# USB2A_CONN.net
KiCad netlist of a schematic drawn in Altium Designer
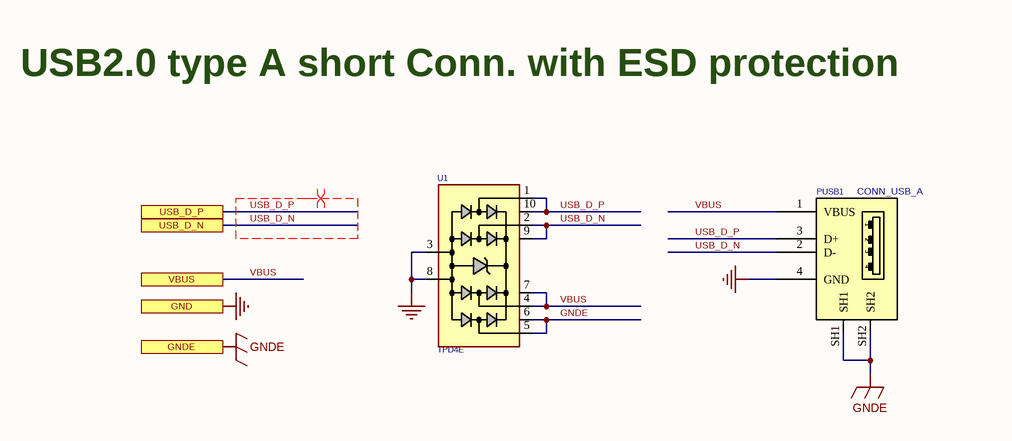
[diagram p0: USB2A_CONN.SchDoc]

(export (version "E")
  (design (tool "Eeschema 10.0.6"))
  (components
    (comp (ref "PUSB1")
      (value "CONN_USB_A")
      (footprint "USB_A_REC_RA_THD_S")
      (description "CONN, USB, A, RECEPTACLE, R/A, THD")
      (fields (field (name "MANF_P#") "USB1125"))
      (libsource (lib "conn_usb") (part "CONN_USB_A_REC_RA_THD_SHORT"))
    )
    (comp (ref "U1")
      (value "TPD4E")
      (footprint "SON50_10_2510")
      (description "TVS, ESD PROTECT, 4CH,")
      (fields (field (name "MANF_P#") "TPD4E05U06DQA") (field (name "MANF") "Texas Instruments"))
      (libsource (lib "protect_tvs_esd_fuse") (part "TVS_X4_TPD4E05U06"))
    )
  )
  (nets
    (net (code "1") (name "/USB_D_N") (class "Default")
      (node (ref "PUSB1") (pin "2") (pinfunction "D-_2") (pintype "passive"))
      (node (ref "U1") (pin "2") (pinfunction "2_2") (pintype "passive"))
      (node (ref "U1") (pin "9") (pinfunction "9_9") (pintype "passive"))
    )
    (net (code "2") (name "/USB_D_P") (class "Default")
      (node (ref "PUSB1") (pin "3") (pinfunction "D+_3") (pintype "passive"))
      (node (ref "U1") (pin "1") (pinfunction "1_1") (pintype "passive"))
      (node (ref "U1") (pin "10") (pinfunction "10_10") (pintype "passive"))
    )
    (net (code "3") (name "/VBUS") (class "Default")
      (node (ref "PUSB1") (pin "1") (pinfunction "VBUS_1") (pintype "passive"))
      (node (ref "U1") (pin "4") (pinfunction "4_4") (pintype "passive"))
      (node (ref "U1") (pin "7") (pinfunction "7_7") (pintype "passive"))
    )
    (net (code "4") (name "GND") (class "Default")
      (node (ref "PUSB1") (pin "4") (pinfunction "GND_4") (pintype "passive"))
      (node (ref "U1") (pin "3") (pinfunction "3_3") (pintype "passive"))
      (node (ref "U1") (pin "8") (pinfunction "8_8") (pintype "passive"))
    )
    (net (code "5") (name "GNDE") (class "Default")
      (node (ref "PUSB1") (pin "SH1") (pinfunction "SH1_SH1") (pintype "passive"))
      (node (ref "PUSB1") (pin "SH2") (pinfunction "SH2_SH2") (pintype "passive"))
      (node (ref "U1") (pin "5") (pinfunction "5_5") (pintype "passive"))
      (node (ref "U1") (pin "6") (pinfunction "6_6") (pintype "passive"))
    )
  )
)
